# Sonar.net
KiCad netlist of a schematic drawn in Altium Designer
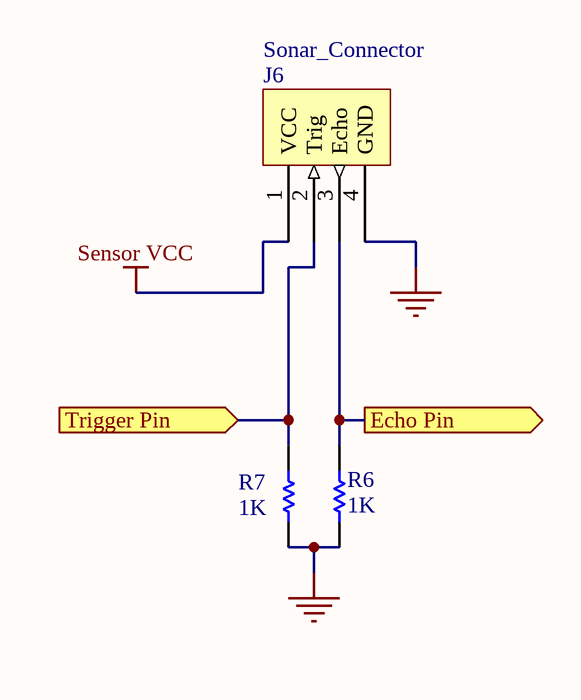
[diagram p0: Sonar.SchDoc]

(export (version "E")
  (design (tool "Eeschema 10.0.6"))
  (components
    (comp (ref "J6")
      (value "Sonar_Connector")
      (footprint "MarvinPcbLib2:SONAR CONNECTOR")
      (description "Female Embase 4 contacts")
      (libsource (lib "POC_Marvin") (part "Sonar_Connector"))
    )
    (comp (ref "R6")
      (value "1K")
      (footprint "1608 / 0603")
      (description "Resistor")
      (fields (field (name "PUBLISHER") "Altium Limited"))
      (libsource (lib "Miscellaneous Devices") (part "Res1"))
    )
    (comp (ref "R7")
      (value "1K")
      (footprint "1608 / 0603")
      (description "Resistor")
      (fields (field (name "PUBLISHER") "Altium Limited"))
      (libsource (lib "Miscellaneous Devices") (part "Res1"))
    )
  )
  (nets
    (net (code "1") (name "/Echo Pin") (class "Default")
      (node (ref "J6") (pin "3") (pinfunction "Echo_3") (pintype "output"))
      (node (ref "R6") (pin "2") (pinfunction "2_2") (pintype "passive"))
    )
    (net (code "2") (name "/Trigger Pin") (class "Default")
      (node (ref "J6") (pin "2") (pinfunction "Trig_2") (pintype "input"))
      (node (ref "R7") (pin "2") (pinfunction "2_2") (pintype "passive"))
    )
    (net (code "3") (name "GND") (class "Default")
      (node (ref "J6") (pin "4") (pinfunction "GND_4") (pintype "power_in"))
      (node (ref "R6") (pin "1") (pinfunction "1_1") (pintype "passive"))
      (node (ref "R7") (pin "1") (pinfunction "1_1") (pintype "passive"))
    )
    (net (code "4") (name "Sensor VCC") (class "Default")
      (node (ref "J6") (pin "1") (pinfunction "VCC_1") (pintype "power_in"))
    )
  )
)
